# FPGA_POWER.net
KiCad netlist of a schematic drawn in Altium Designer
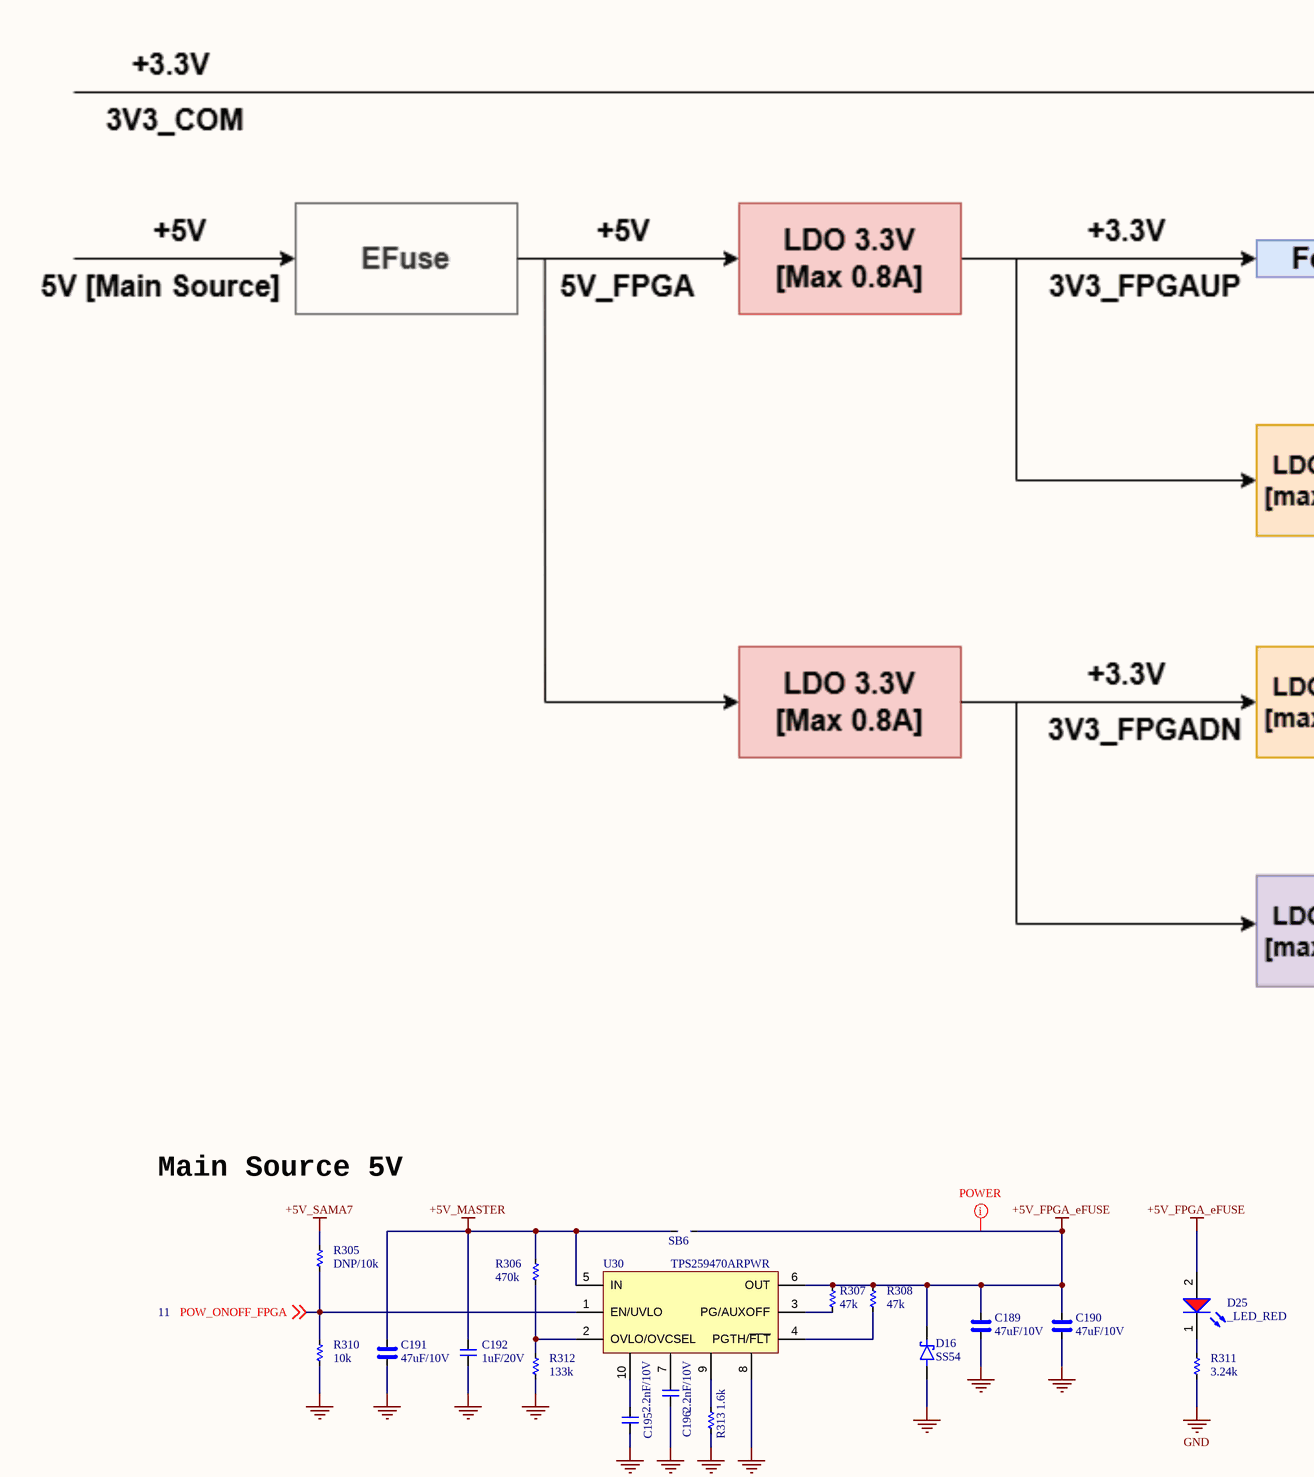
[diagram p0: FPGA_POWER.SchDoc, top left]
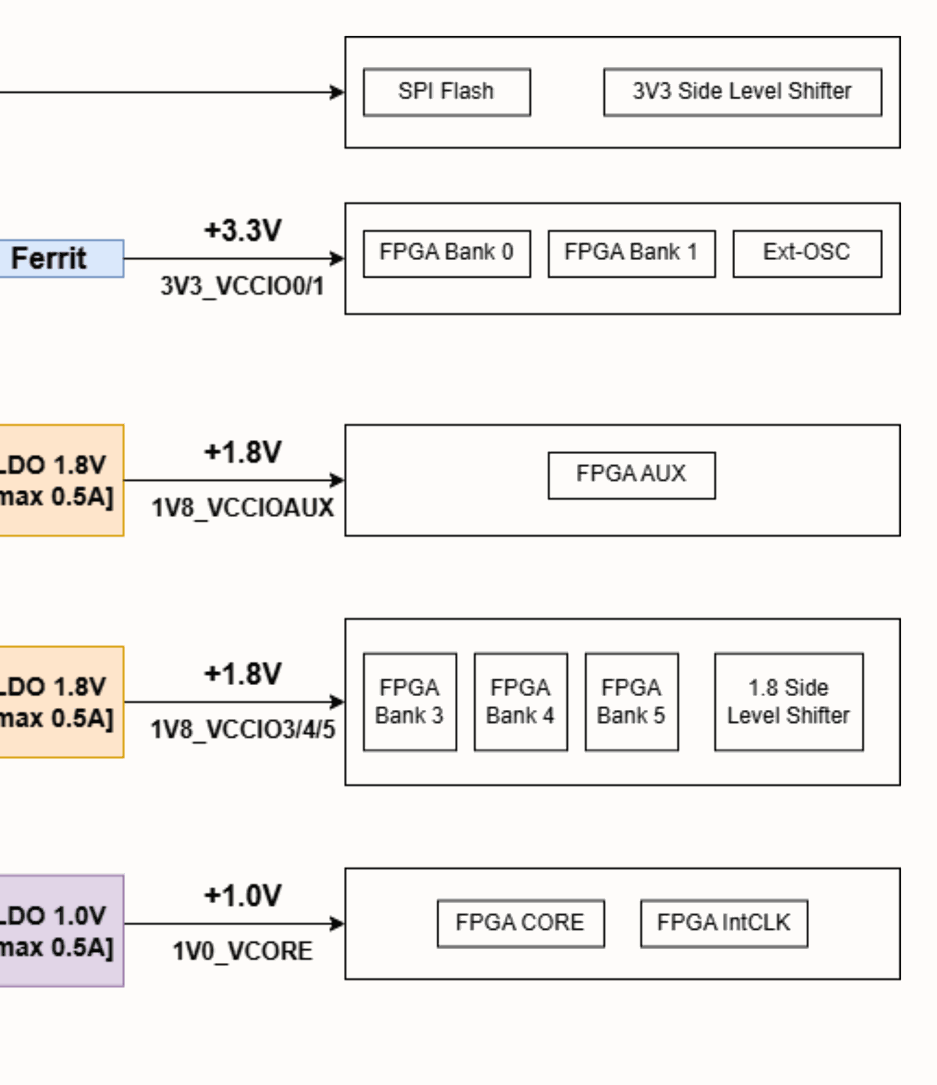
[diagram p1: FPGA_POWER.SchDoc, top right]
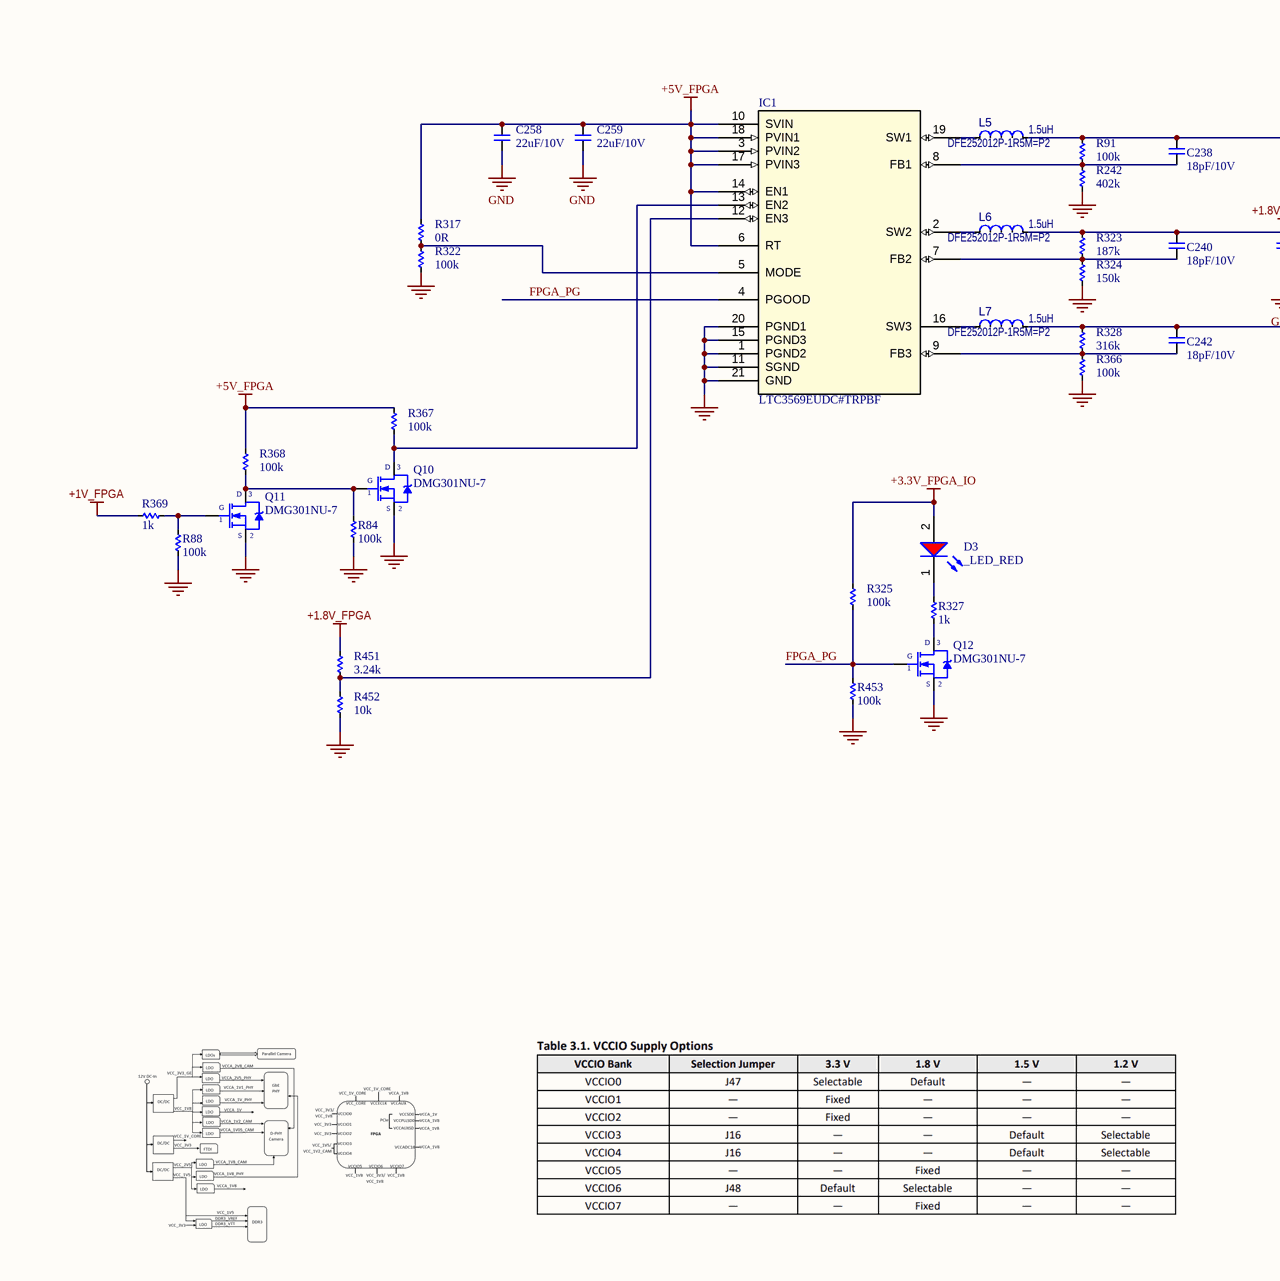
[diagram p2: FPGA_POWER.SchDoc, bottom left]
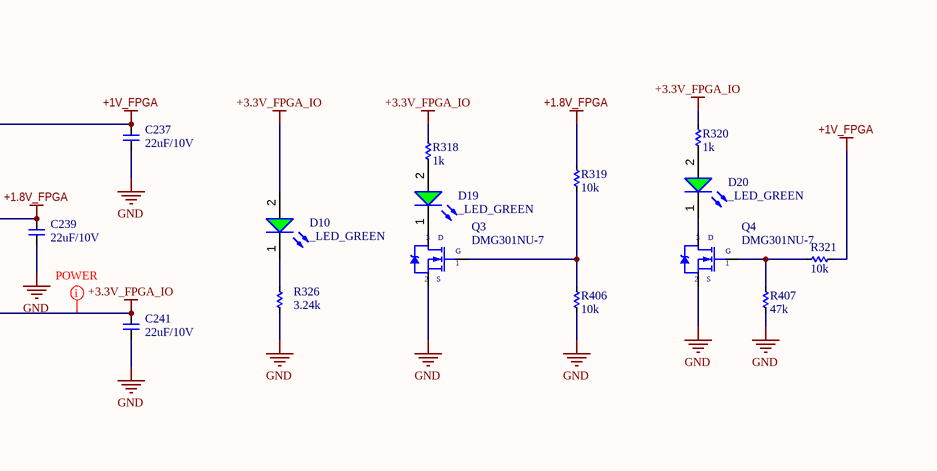
[diagram p3: FPGA_POWER.SchDoc, bottom right]

(export (version "E")
  (design (tool "Eeschema 10.0.6"))
  (components
    (comp (ref "C189")
      (value "47uF/10V")
      (footprint "CAP_C_3225X80")
      (description "CAP CHIP High Value")
      (libsource (lib "IFBschelib") (part "_CAP_C_High_2"))
    )
    (comp (ref "C190")
      (value "47uF/10V")
      (footprint "CAP_C_3225X80")
      (description "CAP CHIP High Value")
      (libsource (lib "IFBschelib") (part "_CAP_C_High_2"))
    )
    (comp (ref "C191")
      (value "47uF/10V")
      (footprint "CAP_C_3225X80")
      (description "CAP CHIP High Value")
      (libsource (lib "IFBschelib") (part "_CAP_C_High_2"))
    )
    (comp (ref "C192")
      (value "1uF/20V")
      (footprint "CAP_C_1005X50_L")
      (description "CAP CHIP")
      (libsource (lib "IFBschelib") (part "_CAP_C_2"))
    )
    (comp (ref "C195")
      (value "2.2nF/10V")
      (footprint "CAP_C_1005X50_L")
      (description "CAP CHIP")
      (libsource (lib "IFBschelib") (part "_CAP_C_2"))
    )
    (comp (ref "C196")
      (value "2.2nF/10V")
      (footprint "CAP_C_1005X50_L")
      (description "CAP CHIP")
      (libsource (lib "IFBschelib") (part "_CAP_C_2"))
    )
    (comp (ref "C237")
      (value "22uF/10V")
      (footprint "CAP_C_1608X80")
      (description "CAP")
      (libsource (lib "LABLIB") (part "_CAP_C_2"))
    )
    (comp (ref "C238")
      (value "18pF/10V")
      (footprint "CAP_C_1005X50_L")
      (description "CAP")
      (libsource (lib "LABLIB") (part "_CAP_C_2"))
    )
    (comp (ref "C239")
      (value "22uF/10V")
      (footprint "CAP_C_1608X80")
      (description "CAP")
      (libsource (lib "LABLIB") (part "_CAP_C_2"))
    )
    (comp (ref "C240")
      (value "18pF/10V")
      (footprint "CAP_C_1005X50_L")
      (description "CAP")
      (libsource (lib "LABLIB") (part "_CAP_C_2"))
    )
    (comp (ref "C241")
      (value "22uF/10V")
      (footprint "CAP_C_1608X80")
      (description "CAP")
      (libsource (lib "LABLIB") (part "_CAP_C_2"))
    )
    (comp (ref "C242")
      (value "18pF/10V")
      (footprint "CAP_C_1005X50_L")
      (description "CAP")
      (libsource (lib "LABLIB") (part "_CAP_C_2"))
    )
    (comp (ref "C258")
      (value "22uF/10V")
      (footprint "CAP_C_1608X80")
      (description "CAP")
      (libsource (lib "LABLIB") (part "_CAP_C_2"))
    )
    (comp (ref "C259")
      (value "22uF/10V")
      (footprint "CAP_C_1608X80")
      (description "CAP")
      (libsource (lib "LABLIB") (part "_CAP_C_2"))
    )
    (comp (ref "D3")
      (value "_LED_RED")
      (footprint "LED_0603")
      (description "LED RED CLEAR 0603 SMD")
      (libsource (lib "IFBschelib") (part "LED_RED"))
    )
    (comp (ref "D10")
      (value "_LED_GREEN")
      (footprint "LED_0603")
      (description "LED GREEN CLEAR 0603 SMD")
      (libsource (lib "IFBschelib") (part "LED_GREEN"))
    )
    (comp (ref "D16")
      (value "SS54")
      (footprint "DO-214AC_SMA")
      (description "DIODE SCHOTTKY")
      (libsource (lib "LABLIB") (part "DIODE SCHOTTKY"))
    )
    (comp (ref "D19")
      (value "_LED_GREEN")
      (footprint "LED_0603")
      (description "LED GREEN CLEAR 0603 SMD")
      (libsource (lib "IFBschelib") (part "LED_GREEN"))
    )
    (comp (ref "D20")
      (value "_LED_GREEN")
      (footprint "LED_0603")
      (description "LED GREEN CLEAR 0603 SMD")
      (libsource (lib "IFBschelib") (part "LED_GREEN"))
    )
    (comp (ref "D25")
      (value "_LED_RED")
      (footprint "LED_0603")
      (description "LED RED CLEAR 0603 SMD")
      (libsource (lib "IFBschelib") (part "LED_RED"))
    )
    (comp (ref "IC1")
      (value "LTC3569EUDC#TRPBF")
      (footprint "QFN20_UDC_3X4_ADI")
      (description "Triple Buck Regulator with 1.2A and Two 600mA Outputs and Individual Programmable References")
      (fields (field (name "COPYRIGHT") "Copyright (C) 2025 Ultra Librarian. All rights reserved."))
      (libsource (lib "LABLIB") (part "LTC3569EUDCTRPBF"))
    )
    (comp (ref "L5")
      (value "1.5uH")
      (footprint "IND_C_1008")
      (description "Inductor")
      (fields
        (field (name "MANUFACTURER PART NUMBER 1") "DFE252012P-1R5M=P2")
        (field (name "Comment") "DFE252012P-1R5M=P2")
        (field (name "OWNER") "Razvan Cristescu")
      )
      (libsource (lib "LABLIB") (part "Inductor"))
    )
    (comp (ref "L6")
      (value "1.5uH")
      (footprint "IND_C_1008")
      (description "Inductor")
      (fields
        (field (name "MANUFACTURER PART NUMBER 1") "DFE252012P-1R5M=P2")
        (field (name "Comment") "DFE252012P-1R5M=P2")
        (field (name "OWNER") "Razvan Cristescu")
      )
      (libsource (lib "LABLIB") (part "Inductor"))
    )
    (comp (ref "L7")
      (value "1.5uH")
      (footprint "IND_C_1008")
      (description "Inductor")
      (fields
        (field (name "MANUFACTURER PART NUMBER 1") "DFE252012P-1R5M=P2")
        (field (name "Comment") "DFE252012P-1R5M=P2")
        (field (name "OWNER") "Razvan Cristescu")
      )
      (libsource (lib "LABLIB") (part "Inductor"))
    )
    (comp (ref "Q3")
      (value "DMG301NU-7")
      (footprint "SOT95P240X120-3N")
      (libsource (lib "LABLIB") (part "MOSFET_N_GSD"))
    )
    (comp (ref "Q4")
      (value "DMG301NU-7")
      (footprint "SOT95P240X120-3N")
      (libsource (lib "LABLIB") (part "MOSFET_N_GSD"))
    )
    (comp (ref "Q10")
      (value "DMG301NU-7")
      (footprint "SOT95P240X120-3N")
      (libsource (lib "LABLIB") (part "MOSFET_N_GSD"))
    )
    (comp (ref "Q11")
      (value "DMG301NU-7")
      (footprint "SOT95P240X120-3N")
      (libsource (lib "LABLIB") (part "MOSFET_N_GSD"))
    )
    (comp (ref "Q12")
      (value "DMG301NU-7")
      (footprint "SOT95P240X120-3N")
      (libsource (lib "LABLIB") (part "MOSFET_N_GSD"))
    )
    (comp (ref "R84")
      (value "100k")
      (footprint "RES_C_1005x30_L")
      (description "RES")
      (libsource (lib "LABLIB") (part "_RES_B_2"))
    )
    (comp (ref "R88")
      (value "100k")
      (footprint "RES_C_1005x30_L")
      (description "RES")
      (libsource (lib "LABLIB") (part "_RES_B_2"))
    )
    (comp (ref "R91")
      (value "100k")
      (footprint "RES_C_1005x30_L")
      (description "RES")
      (libsource (lib "LABLIB") (part "_RES_B_2"))
    )
    (comp (ref "R242")
      (value "402k")
      (footprint "RES_C_1005x30_L")
      (description "RES")
      (libsource (lib "LABLIB") (part "_RES_B_2"))
    )
    (comp (ref "R305")
      (value "DNP/10k")
      (footprint "RES_C_1005x30_L")
      (description "RES")
      (libsource (lib "LABLIB") (part "_RES_B_2"))
    )
    (comp (ref "R306")
      (value "470k")
      (footprint "RES_C_1005x30_L")
      (description "RES")
      (libsource (lib "LABLIB") (part "_RES_B_2"))
    )
    (comp (ref "R307")
      (value "47k")
      (footprint "RES_C_1005x30_L")
      (description "RES")
      (libsource (lib "IFBschelib") (part "_RES_B_2"))
    )
    (comp (ref "R308")
      (value "47k")
      (footprint "RES_C_1005x30_L")
      (description "RES")
      (libsource (lib "IFBschelib") (part "_RES_B_2"))
    )
    (comp (ref "R310")
      (value "10k")
      (footprint "RES_C_1005x30_L")
      (description "RES")
      (libsource (lib "LABLIB") (part "_RES_B_2"))
    )
    (comp (ref "R311")
      (value "3.24k")
      (footprint "RES_C_1005x30_L")
      (description "RES")
      (libsource (lib "IFBschelib") (part "_RES_B_2"))
    )
    (comp (ref "R312")
      (value "133k")
      (footprint "RES_C_1005x30_L")
      (description "RES")
      (libsource (lib "LABLIB") (part "_RES_B_2"))
    )
    (comp (ref "R313")
      (value "1.6k")
      (footprint "RES_C_1005x30_L")
      (description "RES")
      (libsource (lib "IFBschelib") (part "_RES_B_2"))
    )
    (comp (ref "R317")
      (value "0R")
      (footprint "RES_C_1005x30_L")
      (description "RES")
      (libsource (lib "LABLIB") (part "_RES_B_2"))
    )
    (comp (ref "R318")
      (value "1k")
      (footprint "RES_C_1005x30_L")
      (description "RES")
      (libsource (lib "LABLIB") (part "_RES_B_2"))
    )
    (comp (ref "R319")
      (value "10k")
      (footprint "RES_C_1005x30_L")
      (description "RES")
      (libsource (lib "LABLIB") (part "_RES_B_2"))
    )
    (comp (ref "R320")
      (value "1k")
      (footprint "RES_C_1005x30_L")
      (description "RES")
      (libsource (lib "LABLIB") (part "_RES_B_2"))
    )
    (comp (ref "R321")
      (value "10k")
      (footprint "RES_C_1005x30_L")
      (description "RES")
      (libsource (lib "LABLIB") (part "_RES_B_2"))
    )
    (comp (ref "R322")
      (value "100k")
      (footprint "RES_C_1005x30_L")
      (description "RES")
      (libsource (lib "LABLIB") (part "_RES_B_2"))
    )
    (comp (ref "R323")
      (value "187k")
      (footprint "RES_C_1005x30_L")
      (description "RES")
      (libsource (lib "LABLIB") (part "_RES_B_2"))
    )
    (comp (ref "R324")
      (value "150k")
      (footprint "RES_C_1005x30_L")
      (description "RES")
      (libsource (lib "LABLIB") (part "_RES_B_2"))
    )
    (comp (ref "R325")
      (value "100k")
      (footprint "RES_C_1005x30_L")
      (description "RES")
      (libsource (lib "LABLIB") (part "_RES_B_2"))
    )
    (comp (ref "R326")
      (value "3.24k")
      (footprint "RES_C_1005x30_L")
      (description "RES")
      (libsource (lib "IFBschelib") (part "_RES_B_2"))
    )
    (comp (ref "R327")
      (value "1k")
      (footprint "RES_C_1005x30_L")
      (description "RES")
      (libsource (lib "LABLIB") (part "_RES_B_2"))
    )
    (comp (ref "R328")
      (value "316k")
      (footprint "RES_C_1005x30_L")
      (description "RES")
      (libsource (lib "LABLIB") (part "_RES_B_2"))
    )
    (comp (ref "R366")
      (value "100k")
      (footprint "RES_C_1005x30_L")
      (description "RES")
      (libsource (lib "LABLIB") (part "_RES_B_2"))
    )
    (comp (ref "R367")
      (value "100k")
      (footprint "RES_C_1005x30_L")
      (description "RES")
      (libsource (lib "LABLIB") (part "_RES_B_2"))
    )
    (comp (ref "R368")
      (value "100k")
      (footprint "RES_C_1005x30_L")
      (description "RES")
      (libsource (lib "LABLIB") (part "_RES_B_2"))
    )
    (comp (ref "R369")
      (value "1k")
      (footprint "RES_C_1005x30_L")
      (description "RES")
      (libsource (lib "LABLIB") (part "_RES_B_2"))
    )
    (comp (ref "R406")
      (value "10k")
      (footprint "RES_C_1005x30_L")
      (description "RES")
      (libsource (lib "LABLIB") (part "_RES_B_2"))
    )
    (comp (ref "R407")
      (value "47k")
      (footprint "RES_C_1005x30_L")
      (description "RES")
      (libsource (lib "IFBschelib") (part "_RES_B_2"))
    )
    (comp (ref "R451")
      (value "3.24k")
      (footprint "RES_C_1005x30_L")
      (description "RES")
      (libsource (lib "LABLIB") (part "_RES_B_2"))
    )
    (comp (ref "R452")
      (value "10k")
      (footprint "RES_C_1005x30_L")
      (description "RES")
      (libsource (lib "LABLIB") (part "_RES_B_2"))
    )
    (comp (ref "R453")
      (value "100k")
      (footprint "RES_C_1005x30_L")
      (description "RES")
      (libsource (lib "LABLIB") (part "_RES_B_2"))
    )
    (comp (ref "SB6")
      (value "JUMPER")
      (footprint "JUMPER_1608")
      (libsource (lib "IFBschelib") (part "JUMPER"))
    )
    (comp (ref "U30")
      (value "TPS259470ARPWR")
      (footprint "VQFN-HR-10")
      (libsource (lib "IFBschelib") (part "TPS259470ARPWR"))
    )
  )
  (nets
    (net (code "1") (name "+1.8V_FPGA") (class "Default")
      (node (ref "C239") (pin "1") (pinfunction "1_1") (pintype "passive"))
      (node (ref "C240") (pin "1") (pinfunction "1_1") (pintype "passive"))
      (node (ref "L6") (pin "2") (pinfunction "F_2") (pintype "passive"))
      (node (ref "R319") (pin "1") (pinfunction "1_1") (pintype "passive"))
      (node (ref "R323") (pin "2") (pinfunction "2_2") (pintype "passive"))
      (node (ref "R451") (pin "2") (pinfunction "2_2") (pintype "passive"))
    )
    (net (code "2") (name "+1V_FPGA") (class "Default")
      (node (ref "C237") (pin "1") (pinfunction "1_1") (pintype "passive"))
      (node (ref "C238") (pin "1") (pinfunction "1_1") (pintype "passive"))
      (node (ref "L5") (pin "2") (pinfunction "F_2") (pintype "passive"))
      (node (ref "R321") (pin "1") (pinfunction "1_1") (pintype "passive"))
      (node (ref "R369") (pin "2") (pinfunction "2_2") (pintype "passive"))
      (node (ref "R91") (pin "2") (pinfunction "2_2") (pintype "passive"))
    )
    (net (code "3") (name "+3.3V_FPGA_IO") (class "Default")
      (node (ref "C241") (pin "1") (pinfunction "1_1") (pintype "passive"))
      (node (ref "C242") (pin "1") (pinfunction "1_1") (pintype "passive"))
      (node (ref "D10") (pin "2") (pinfunction "A_2") (pintype "passive"))
      (node (ref "D3") (pin "2") (pinfunction "A_2") (pintype "passive"))
      (node (ref "L7") (pin "2") (pinfunction "F_2") (pintype "passive"))
      (node (ref "R318") (pin "2") (pinfunction "2_2") (pintype "passive"))
      (node (ref "R320") (pin "2") (pinfunction "2_2") (pintype "passive"))
      (node (ref "R325") (pin "2") (pinfunction "2_2") (pintype "passive"))
      (node (ref "R328") (pin "2") (pinfunction "2_2") (pintype "passive"))
    )
    (net (code "4") (name "+5V_FPGA") (class "Default")
      (node (ref "C258") (pin "1") (pinfunction "1_1") (pintype "passive"))
      (node (ref "C259") (pin "1") (pinfunction "1_1") (pintype "passive"))
      (node (ref "IC1") (pin "10") (pinfunction "SVIN_10") (pintype "passive"))
      (node (ref "IC1") (pin "14") (pinfunction "EN1_14") (pintype "bidirectional"))
      (node (ref "IC1") (pin "17") (pinfunction "PVIN3_17") (pintype "input"))
      (node (ref "IC1") (pin "18") (pinfunction "PVIN1_18") (pintype "input"))
      (node (ref "IC1") (pin "3") (pinfunction "PVIN2_3") (pintype "input"))
      (node (ref "IC1") (pin "6") (pinfunction "RT_6") (pintype "passive"))
      (node (ref "R317") (pin "2") (pinfunction "2_2") (pintype "passive"))
      (node (ref "R367") (pin "2") (pinfunction "2_2") (pintype "passive"))
      (node (ref "R368") (pin "2") (pinfunction "2_2") (pintype "passive"))
    )
    (net (code "5") (name "+5V_FPGA_eFUSE") (class "Default")
      (node (ref "C189") (pin "2") (pinfunction "2_2") (pintype "passive"))
      (node (ref "C190") (pin "2") (pinfunction "2_2") (pintype "passive"))
      (node (ref "D16") (pin "1") (pinfunction "K_1") (pintype "passive"))
      (node (ref "D25") (pin "2") (pinfunction "A_2") (pintype "passive"))
      (node (ref "R307") (pin "2") (pinfunction "2_2") (pintype "passive"))
      (node (ref "R308") (pin "2") (pinfunction "2_2") (pintype "passive"))
      (node (ref "SB6") (pin "2") (pinfunction "2_2") (pintype "passive"))
      (node (ref "U30") (pin "6") (pinfunction "OUT_6") (pintype "passive"))
    )
    (net (code "6") (name "+5V_MASTER") (class "Default")
      (node (ref "C191") (pin "2") (pinfunction "2_2") (pintype "passive"))
      (node (ref "C192") (pin "2") (pinfunction "2_2") (pintype "passive"))
      (node (ref "R306") (pin "2") (pinfunction "2_2") (pintype "passive"))
      (node (ref "SB6") (pin "1") (pinfunction "1_1") (pintype "passive"))
      (node (ref "U30") (pin "5") (pinfunction "IN_5") (pintype "passive"))
    )
    (net (code "7") (name "+5V_SAMA7") (class "Default")
      (node (ref "R305") (pin "1") (pinfunction "1_1") (pintype "passive"))
    )
    (net (code "8") (name "/FPGA_PG") (class "Default")
      (node (ref "IC1") (pin "4") (pinfunction "PGOOD_4") (pintype "power_in"))
      (node (ref "Q12") (pin "1") (pinfunction "G_1") (pintype "passive"))
      (node (ref "R325") (pin "1") (pinfunction "1_1") (pintype "passive"))
      (node (ref "R453") (pin "1") (pinfunction "1_1") (pintype "passive"))
    )
    (net (code "9") (name "GND") (class "Default")
      (node (ref "C189") (pin "1") (pinfunction "1_1") (pintype "passive"))
      (node (ref "C190") (pin "1") (pinfunction "1_1") (pintype "passive"))
      (node (ref "C191") (pin "1") (pinfunction "1_1") (pintype "passive"))
      (node (ref "C192") (pin "1") (pinfunction "1_1") (pintype "passive"))
      (node (ref "C195") (pin "1") (pinfunction "1_1") (pintype "passive"))
      (node (ref "C196") (pin "1") (pinfunction "1_1") (pintype "passive"))
      (node (ref "C237") (pin "2") (pinfunction "2_2") (pintype "passive"))
      (node (ref "C239") (pin "2") (pinfunction "2_2") (pintype "passive"))
      (node (ref "C241") (pin "2") (pinfunction "2_2") (pintype "passive"))
      (node (ref "C258") (pin "2") (pinfunction "2_2") (pintype "passive"))
      (node (ref "C259") (pin "2") (pinfunction "2_2") (pintype "passive"))
      (node (ref "D16") (pin "2") (pinfunction "A_2") (pintype "passive"))
      (node (ref "IC1") (pin "1") (pinfunction "PGND2_1") (pintype "power_in"))
      (node (ref "IC1") (pin "11") (pinfunction "SGND_11") (pintype "power_in"))
      (node (ref "IC1") (pin "15") (pinfunction "PGND3_15") (pintype "power_in"))
      (node (ref "IC1") (pin "20") (pinfunction "PGND1_20") (pintype "power_in"))
      (node (ref "IC1") (pin "21") (pinfunction "GND_21") (pintype "power_in"))
      (node (ref "Q10") (pin "2") (pinfunction "S_2") (pintype "passive"))
      (node (ref "Q11") (pin "2") (pinfunction "S_2") (pintype "passive"))
      (node (ref "Q12") (pin "2") (pinfunction "S_2") (pintype "passive"))
      (node (ref "Q3") (pin "2") (pinfunction "S_2") (pintype "passive"))
      (node (ref "Q4") (pin "2") (pinfunction "S_2") (pintype "passive"))
      (node (ref "R242") (pin "1") (pinfunction "1_1") (pintype "passive"))
      (node (ref "R310") (pin "2") (pinfunction "2_2") (pintype "passive"))
      (node (ref "R311") (pin "1") (pinfunction "1_1") (pintype "passive"))
      (node (ref "R312") (pin "1") (pinfunction "1_1") (pintype "passive"))
      (node (ref "R313") (pin "1") (pinfunction "1_1") (pintype "passive"))
      (node (ref "R322") (pin "1") (pinfunction "1_1") (pintype "passive"))
      (node (ref "R324") (pin "1") (pinfunction "1_1") (pintype "passive"))
      (node (ref "R326") (pin "1") (pinfunction "1_1") (pintype "passive"))
      (node (ref "R366") (pin "1") (pinfunction "1_1") (pintype "passive"))
      (node (ref "R406") (pin "2") (pinfunction "2_2") (pintype "passive"))
      (node (ref "R407") (pin "1") (pinfunction "1_1") (pintype "passive"))
      (node (ref "R452") (pin "1") (pinfunction "1_1") (pintype "passive"))
      (node (ref "R453") (pin "2") (pinfunction "2_2") (pintype "passive"))
      (node (ref "R84") (pin "2") (pinfunction "2_2") (pintype "passive"))
      (node (ref "R88") (pin "2") (pinfunction "2_2") (pintype "passive"))
      (node (ref "U30") (pin "8") (pinfunction "8_8") (pintype "passive"))
    )
    (net (code "10") (name "Net-(C195-Pad2)") (class "Default")
      (node (ref "C195") (pin "2") (pinfunction "2_2") (pintype "passive"))
      (node (ref "U30") (pin "10") (pinfunction "10_10") (pintype "passive"))
    )
    (net (code "11") (name "Net-(C196-Pad2)") (class "Default")
      (node (ref "C196") (pin "2") (pinfunction "2_2") (pintype "passive"))
      (node (ref "U30") (pin "7") (pinfunction "7_7") (pintype "passive"))
    )
    (net (code "12") (name "Net-(D3-K)") (class "Default")
      (node (ref "D3") (pin "1") (pinfunction "K_1") (pintype "passive"))
      (node (ref "R327") (pin "2") (pinfunction "2_2") (pintype "passive"))
    )
    (net (code "13") (name "Net-(D10-K)") (class "Default")
      (node (ref "D10") (pin "1") (pinfunction "K_1") (pintype "passive"))
      (node (ref "R326") (pin "2") (pinfunction "2_2") (pintype "passive"))
    )
    (net (code "14") (name "Net-(D19-A)") (class "Default")
      (node (ref "D19") (pin "2") (pinfunction "A_2") (pintype "passive"))
      (node (ref "R318") (pin "1") (pinfunction "1_1") (pintype "passive"))
    )
    (net (code "15") (name "Net-(D19-K)") (class "Default")
      (node (ref "D19") (pin "1") (pinfunction "K_1") (pintype "passive"))
      (node (ref "Q3") (pin "3") (pinfunction "D_3") (pintype "passive"))
    )
    (net (code "16") (name "Net-(D20-A)") (class "Default")
      (node (ref "D20") (pin "2") (pinfunction "A_2") (pintype "passive"))
      (node (ref "R320") (pin "1") (pinfunction "1_1") (pintype "passive"))
    )
    (net (code "17") (name "Net-(D20-K)") (class "Default")
      (node (ref "D20") (pin "1") (pinfunction "K_1") (pintype "passive"))
      (node (ref "Q4") (pin "3") (pinfunction "D_3") (pintype "passive"))
    )
    (net (code "18") (name "Net-(D25-K)") (class "Default")
      (node (ref "D25") (pin "1") (pinfunction "K_1") (pintype "passive"))
      (node (ref "R311") (pin "2") (pinfunction "2_2") (pintype "passive"))
    )
    (net (code "19") (name "Net-(IC1-EN2)") (class "Default")
      (node (ref "IC1") (pin "13") (pinfunction "EN2_13") (pintype "bidirectional"))
      (node (ref "Q10") (pin "3") (pinfunction "D_3") (pintype "passive"))
      (node (ref "R367") (pin "1") (pinfunction "1_1") (pintype "passive"))
    )
    (net (code "20") (name "Net-(IC1-EN3)") (class "Default")
      (node (ref "IC1") (pin "12") (pinfunction "EN3_12") (pintype "bidirectional"))
      (node (ref "R451") (pin "1") (pinfunction "1_1") (pintype "passive"))
      (node (ref "R452") (pin "2") (pinfunction "2_2") (pintype "passive"))
    )
    (net (code "21") (name "Net-(IC1-FB1)") (class "Default")
      (node (ref "C238") (pin "2") (pinfunction "2_2") (pintype "passive"))
      (node (ref "IC1") (pin "8") (pinfunction "FB1_8") (pintype "bidirectional"))
      (node (ref "R242") (pin "2") (pinfunction "2_2") (pintype "passive"))
      (node (ref "R91") (pin "1") (pinfunction "1_1") (pintype "passive"))
    )
    (net (code "22") (name "Net-(IC1-FB2)") (class "Default")
      (node (ref "C240") (pin "2") (pinfunction "2_2") (pintype "passive"))
      (node (ref "IC1") (pin "7") (pinfunction "FB2_7") (pintype "bidirectional"))
      (node (ref "R323") (pin "1") (pinfunction "1_1") (pintype "passive"))
      (node (ref "R324") (pin "2") (pinfunction "2_2") (pintype "passive"))
    )
    (net (code "23") (name "Net-(IC1-FB3)") (class "Default")
      (node (ref "C242") (pin "2") (pinfunction "2_2") (pintype "passive"))
      (node (ref "IC1") (pin "9") (pinfunction "FB3_9") (pintype "bidirectional"))
      (node (ref "R328") (pin "1") (pinfunction "1_1") (pintype "passive"))
      (node (ref "R366") (pin "2") (pinfunction "2_2") (pintype "passive"))
    )
    (net (code "24") (name "Net-(IC1-MODE)") (class "Default")
      (node (ref "IC1") (pin "5") (pinfunction "MODE_5") (pintype "passive"))
      (node (ref "R317") (pin "1") (pinfunction "1_1") (pintype "passive"))
      (node (ref "R322") (pin "2") (pinfunction "2_2") (pintype "passive"))
    )
    (net (code "25") (name "Net-(IC1-SW1)") (class "Default")
      (node (ref "IC1") (pin "19") (pinfunction "SW1_19") (pintype "bidirectional"))
      (node (ref "L5") (pin "1") (pinfunction "S_1") (pintype "passive"))
    )
    (net (code "26") (name "Net-(IC1-SW2)") (class "Default")
      (node (ref "IC1") (pin "2") (pinfunction "SW2_2") (pintype "bidirectional"))
      (node (ref "L6") (pin "1") (pinfunction "S_1") (pintype "passive"))
    )
    (net (code "27") (name "Net-(IC1-SW3)") (class "Default")
      (node (ref "IC1") (pin "16") (pinfunction "SW3_16") (pintype "passive"))
      (node (ref "L7") (pin "1") (pinfunction "S_1") (pintype "passive"))
    )
    (net (code "28") (name "Net-(Q3-G)") (class "Default")
      (node (ref "Q3") (pin "1") (pinfunction "G_1") (pintype "passive"))
      (node (ref "R319") (pin "2") (pinfunction "2_2") (pintype "passive"))
      (node (ref "R406") (pin "1") (pinfunction "1_1") (pintype "passive"))
    )
    (net (code "29") (name "Net-(Q4-G)") (class "Default")
      (node (ref "Q4") (pin "1") (pinfunction "G_1") (pintype "passive"))
      (node (ref "R321") (pin "2") (pinfunction "2_2") (pintype "passive"))
      (node (ref "R407") (pin "2") (pinfunction "2_2") (pintype "passive"))
    )
    (net (code "30") (name "Net-(Q10-G)") (class "Default")
      (node (ref "Q10") (pin "1") (pinfunction "G_1") (pintype "passive"))
      (node (ref "Q11") (pin "3") (pinfunction "D_3") (pintype "passive"))
      (node (ref "R368") (pin "1") (pinfunction "1_1") (pintype "passive"))
      (node (ref "R84") (pin "1") (pinfunction "1_1") (pintype "passive"))
    )
    (net (code "31") (name "Net-(Q11-G)") (class "Default")
      (node (ref "Q11") (pin "1") (pinfunction "G_1") (pintype "passive"))
      (node (ref "R369") (pin "1") (pinfunction "1_1") (pintype "passive"))
      (node (ref "R88") (pin "1") (pinfunction "1_1") (pintype "passive"))
    )
    (net (code "32") (name "Net-(Q12-D)") (class "Default")
      (node (ref "Q12") (pin "3") (pinfunction "D_3") (pintype "passive"))
      (node (ref "R327") (pin "1") (pinfunction "1_1") (pintype "passive"))
    )
    (net (code "33") (name "Net-(R313-Pad2)") (class "Default")
      (node (ref "R313") (pin "2") (pinfunction "2_2") (pintype "passive"))
      (node (ref "U30") (pin "9") (pinfunction "9_9") (pintype "passive"))
    )
    (net (code "34") (name "Net-(U30-OVLO{slash}OVCSEL)") (class "Default")
      (node (ref "R306") (pin "1") (pinfunction "1_1") (pintype "passive"))
      (node (ref "R312") (pin "2") (pinfunction "2_2") (pintype "passive"))
      (node (ref "U30") (pin "2") (pinfunction "OVLO/OVCSEL_2") (pintype "passive"))
    )
    (net (code "35") (name "Net-(U30-PGTH{slash}~{FLT})") (class "Default")
      (node (ref "R308") (pin "1") (pinfunction "1_1") (pintype "passive"))
      (node (ref "U30") (pin "4") (pinfunction "PGTH/~{FLT}_4") (pintype "passive"))
    )
    (net (code "36") (name "Net-(U30-PG{slash}AUXOFF)") (class "Default")
      (node (ref "R307") (pin "1") (pinfunction "1_1") (pintype "passive"))
      (node (ref "U30") (pin "3") (pinfunction "PG/AUXOFF_3") (pintype "passive"))
    )
    (net (code "37") (name "POW_ONOFF_FPGA") (class "Default")
      (node (ref "R305") (pin "2") (pinfunction "2_2") (pintype "passive"))
      (node (ref "R310") (pin "1") (pinfunction "1_1") (pintype "passive"))
      (node (ref "U30") (pin "1") (pinfunction "EN/UVLO_1") (pintype "passive"))
    )
  )
)
